# temp_meas.net
KiCad netlist of a schematic drawn in Altium Designer
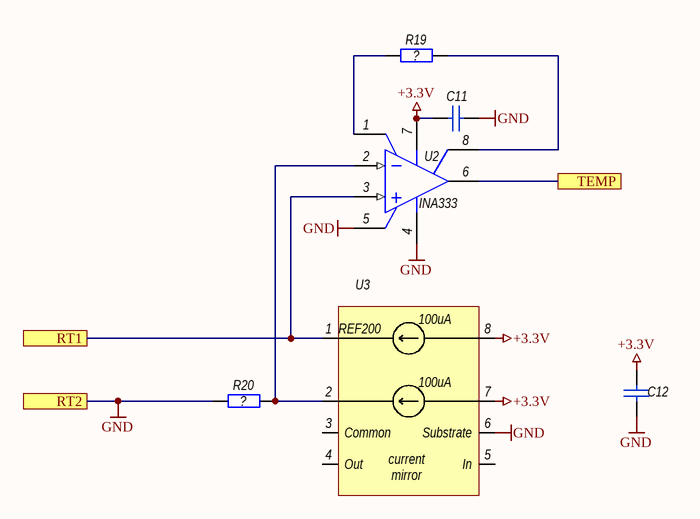
[diagram p0: temp_meas.SchDoc]

(export (version "E")
  (design (tool "Eeschema 10.0.6"))
  (components
    (comp (ref "C11")
      (value "0603 1u 6.3V")
      (footprint "CAP_0805")
      (description "Конденсатор")
      (libsource (lib "SCH_LIB") (part "Capacitor"))
    )
    (comp (ref "C12")
      (value "0603 1u 6.3V")
      (footprint "CAP_0603")
      (description "Конденсатор")
      (libsource (lib "SCH_LIB") (part "Capacitor"))
    )
    (comp (ref "R19")
      (value "?")
      (footprint "RES_0603")
      (description "Резистор")
      (libsource (lib "SCH_LIB") (part "Resisitor"))
    )
    (comp (ref "R20")
      (value "?")
      (footprint "RES_0603")
      (description "Резистор")
      (libsource (lib "SCH_LIB") (part "Resisitor"))
    )
    (comp (ref "U2")
      (value "INA333")
      (footprint "PCB_LIB:MSOP-8")
      (description "Инструментальный усилитель")
      (libsource (lib "SCH_LIB") (part "INA333"))
    )
    (comp (ref "U3")
      (value "REF200")
      (footprint "PCB_LIB:SO8-150")
      (description "Источник опорного тока")
      (libsource (lib "SCH_LIB") (part "REF200"))
    )
  )
  (nets
    (net (code "1") (name "+3.3V") (class "Default")
      (node (ref "C11") (pin "2") (pinfunction "2_2") (pintype "passive"))
      (node (ref "C12") (pin "2") (pinfunction "2_2") (pintype "passive"))
      (node (ref "U2") (pin "7") (pinfunction "V+_7") (pintype "power_in"))
      (node (ref "U3") (pin "7") (pinfunction "11_7") (pintype "passive"))
      (node (ref "U3") (pin "8") (pinfunction "11_8") (pintype "passive"))
    )
    (net (code "2") (name "/RT1") (class "Default")
      (node (ref "U2") (pin "3") (pinfunction "IN+_3") (pintype "input"))
      (node (ref "U3") (pin "1") (pinfunction "10_1") (pintype "passive"))
    )
    (net (code "3") (name "/TEMP") (class "Default")
      (node (ref "U2") (pin "6") (pinfunction "OUT_6") (pintype "open_collector"))
    )
    (net (code "4") (name "GND") (class "Default")
      (node (ref "C11") (pin "1") (pinfunction "1_1") (pintype "passive"))
      (node (ref "C12") (pin "1") (pinfunction "1_1") (pintype "passive"))
      (node (ref "R20") (pin "1") (pinfunction "1_1") (pintype "passive"))
      (node (ref "U2") (pin "4") (pinfunction "V-_4") (pintype "power_in"))
      (node (ref "U2") (pin "5") (pinfunction "REF_5") (pintype "power_in"))
      (node (ref "U3") (pin "6") (pinfunction "Substrate_6") (pintype "passive"))
    )
    (net (code "5") (name "Net-(R19-Pad1)") (class "Default")
      (node (ref "R19") (pin "1") (pinfunction "1_1") (pintype "passive"))
      (node (ref "U2") (pin "1") (pinfunction "RG_1") (pintype "power_in"))
    )
    (net (code "6") (name "Net-(R19-Pad2)") (class "Default")
      (node (ref "R19") (pin "2") (pinfunction "2_2") (pintype "passive"))
      (node (ref "U2") (pin "8") (pinfunction "RG_8") (pintype "power_in"))
    )
    (net (code "7") (name "Net-(U2-IN-)") (class "Default")
      (node (ref "R20") (pin "2") (pinfunction "2_2") (pintype "passive"))
      (node (ref "U2") (pin "2") (pinfunction "IN-_2") (pintype "input"))
      (node (ref "U3") (pin "2") (pinfunction "10_2") (pintype "passive"))
    )
    (net (code "8") (name "unconnected-(U3-Common-Pad3)") (class "Default")
      (node (ref "U3") (pin "3") (pinfunction "Common_3") (pintype "passive"))
    )
    (net (code "9") (name "unconnected-(U3-In-Pad5)") (class "Default")
      (node (ref "U3") (pin "5") (pinfunction "In_5") (pintype "passive"))
    )
    (net (code "10") (name "unconnected-(U3-Out-Pad4)") (class "Default")
      (node (ref "U3") (pin "4") (pinfunction "Out_4") (pintype "passive"))
    )
  )
)
